# Memory_Display.net
KiCad netlist of a schematic drawn in EAGLE
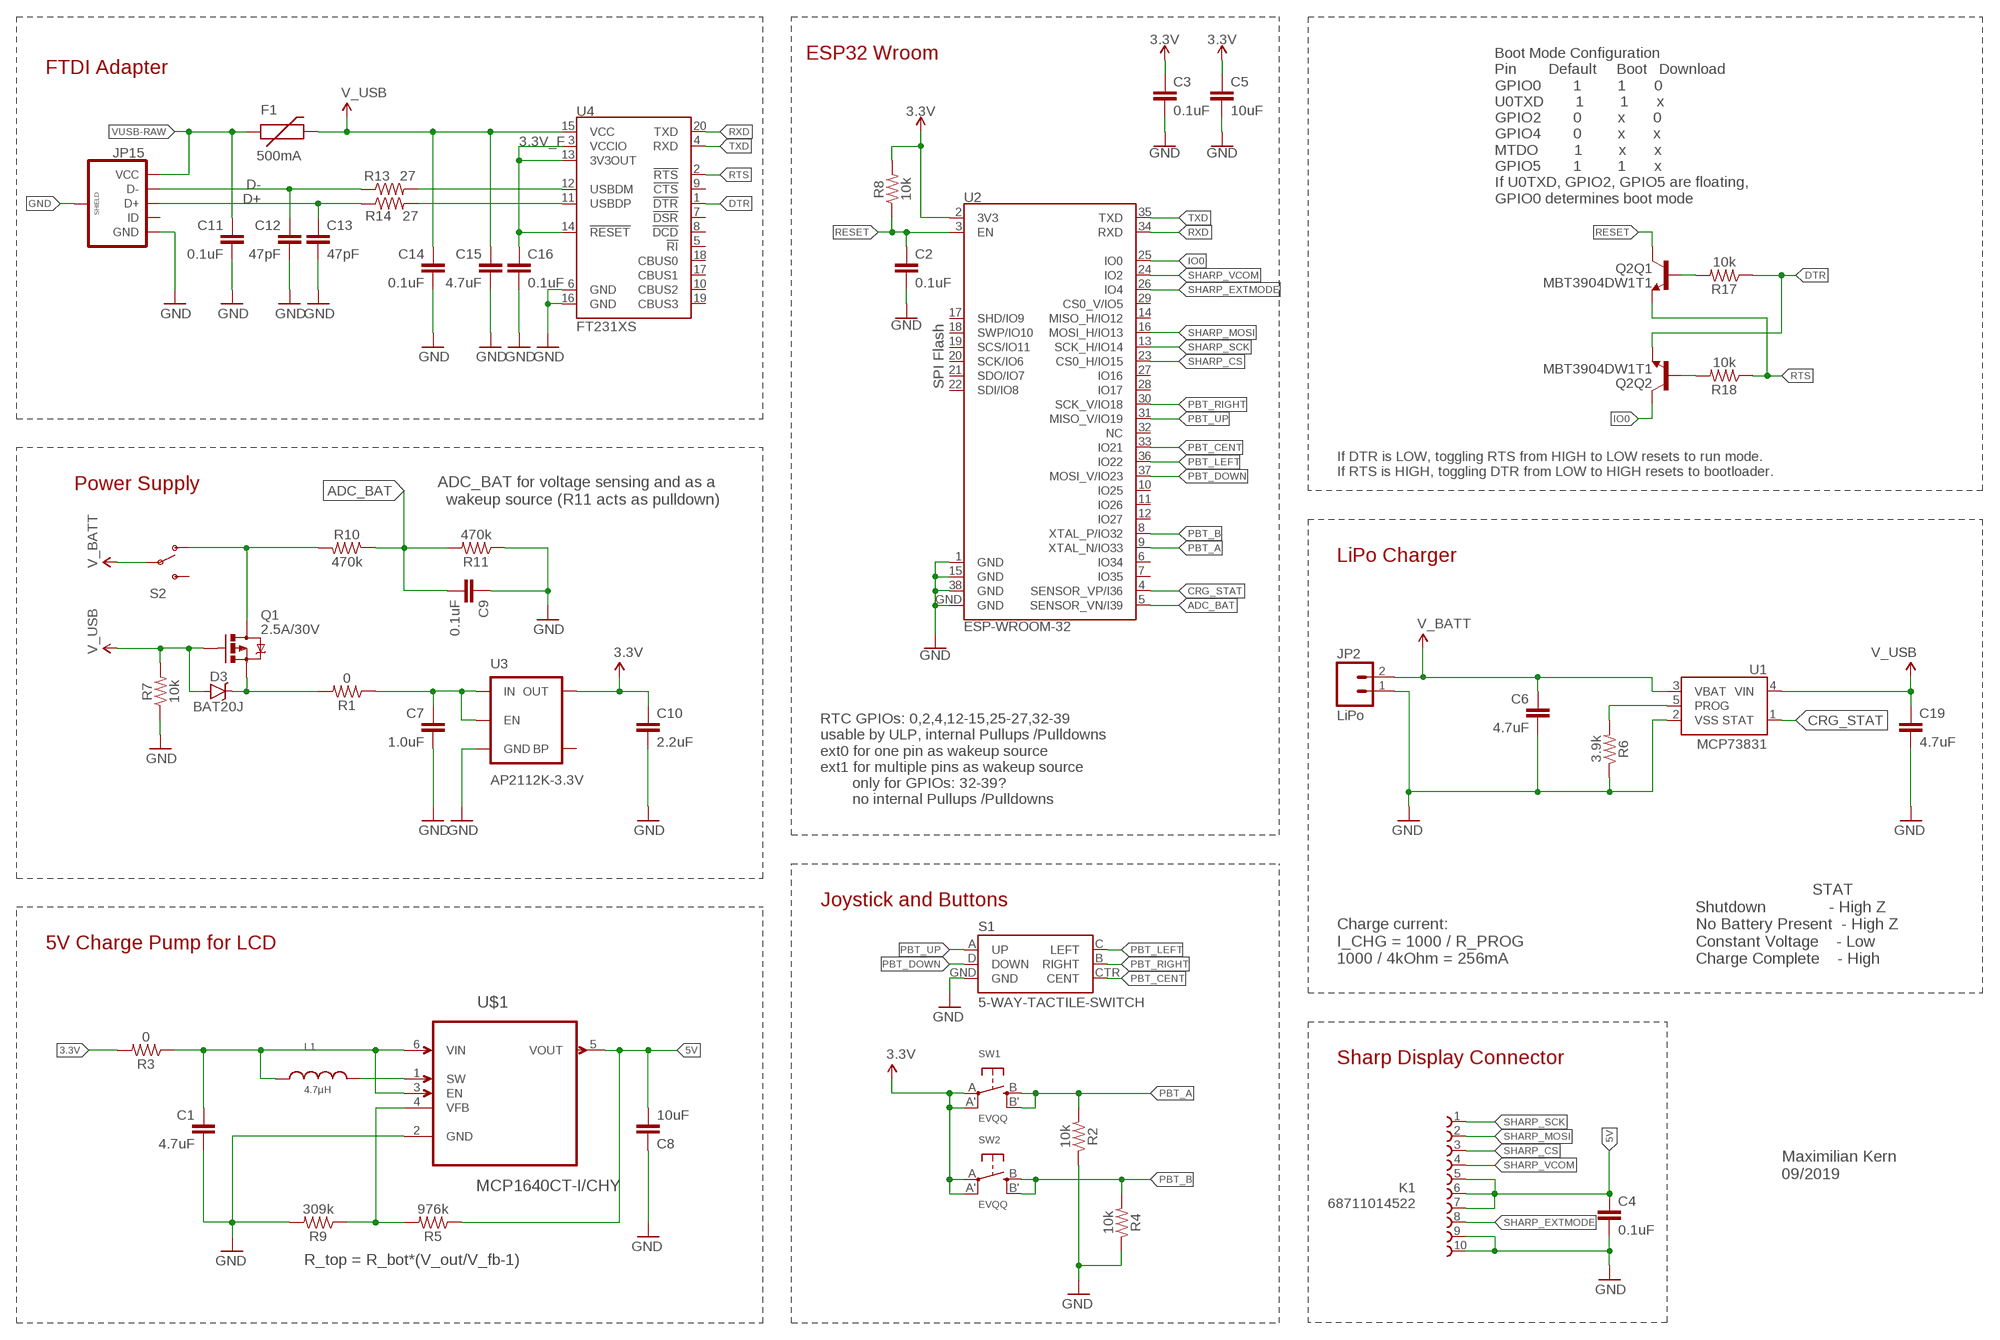
[diagram p0: schematic, sheet 1]

(export (version "E")
  (design (tool "Eeschema 10.0.6"))
  (components
    (comp (ref "C1")
      (value "4.7uF")
      (footprint "eagle-import:0603")
      (libsource (lib "eagle-import") (part "47PF-0603-50V-5%"))
    )
    (comp (ref "C2")
      (value "0.1uF")
      (footprint "eagle-import:0603")
      (libsource (lib "eagle-import") (part "0.1UF-0603-25V-(+80/-20%)"))
    )
    (comp (ref "C3")
      (value "0.1uF")
      (footprint "eagle-import:0603")
      (libsource (lib "eagle-import") (part "0.1UF-0603-25V-(+80/-20%)"))
    )
    (comp (ref "C4")
      (value "0.1uF")
      (footprint "eagle-import:0603")
      (libsource (lib "eagle-import") (part "0.1UF-0603-25V-(+80/-20%)"))
    )
    (comp (ref "C5")
      (value "10uF")
      (footprint "eagle-import:0603")
      (libsource (lib "eagle-import") (part "10UF-0603-6.3V-20%"))
    )
    (comp (ref "C6")
      (value "4.7uF")
      (footprint "eagle-import:0603")
      (libsource (lib "eagle-import") (part "4.7UF0603"))
    )
    (comp (ref "C7")
      (value "1.0uF")
      (footprint "eagle-import:0805")
      (libsource (lib "eagle-import") (part "1.0UF-0805-25V-(+80/-20%)"))
    )
    (comp (ref "C8")
      (value "10uF")
      (footprint "eagle-import:0603")
      (libsource (lib "eagle-import") (part "47PF-0603-50V-5%"))
    )
    (comp (ref "C9")
      (value "0.1uF")
      (footprint "eagle-import:0603")
      (libsource (lib "eagle-import") (part "0.1UF-0603-25V-(+80/-20%)"))
    )
    (comp (ref "C10")
      (value "2.2uF")
      (footprint "eagle-import:0805")
      (libsource (lib "eagle-import") (part "1.0UF-0805-25V-(+80/-20%)"))
    )
    (comp (ref "C11")
      (value "0.1uF")
      (footprint "eagle-import:0603")
      (libsource (lib "eagle-import") (part "0.1UF-0603-25V-(+80/-20%)"))
    )
    (comp (ref "C12")
      (value "47pF")
      (footprint "eagle-import:0603")
      (libsource (lib "eagle-import") (part "47PF-0603-50V-5%"))
    )
    (comp (ref "C13")
      (value "47pF")
      (footprint "eagle-import:0603")
      (libsource (lib "eagle-import") (part "47PF-0603-50V-5%"))
    )
    (comp (ref "C14")
      (value "0.1uF")
      (footprint "eagle-import:0603")
      (libsource (lib "eagle-import") (part "0.1UF-0603-25V-(+80/-20%)"))
    )
    (comp (ref "C15")
      (value "4.7uF")
      (footprint "eagle-import:0603-CAP")
      (libsource (lib "eagle-import") (part "4.7UF-6.3V-10%(0603)0603"))
    )
    (comp (ref "C16")
      (value "0.1uF")
      (footprint "eagle-import:0603")
      (libsource (lib "eagle-import") (part "0.1UF-0603-25V-(+80/-20%)"))
    )
    (comp (ref "C19")
      (value "4.7uF")
      (footprint "eagle-import:0603")
      (libsource (lib "eagle-import") (part "4.7UF0603"))
    )
    (comp (ref "D3")
      (value "BAT20J")
      (footprint "eagle-import:SOD-323")
      (libsource (lib "eagle-import") (part "DIODE-SCHOTTKY-BAT20J"))
    )
    (comp (ref "F1")
      (value "500mA")
      (footprint "eagle-import:PTC-1206")
      (libsource (lib "eagle-import") (part "PTCSMD"))
    )
    (comp (ref "JP2")
      (value "LiPo")
      (footprint "eagle-import:JST-2-PTH")
      (libsource (lib "eagle-import") (part "M02JST-PTH-2"))
    )
    (comp (ref "JP15")
      (value "USB_MICROB_PLUGCONN-11752")
      (footprint "eagle-import:USB-B-MICRO-SMD_V03")
      (libsource (lib "eagle-import") (part "USB_MICROB_PLUGCONN-11752"))
    )
    (comp (ref "K1")
      (value "68711014522")
      (footprint "eagle-import:68711014522")
      (libsource (lib "eagle-import") (part "68711014522"))
    )
    (comp (ref "L1")
      (value "4.7µH")
      (footprint "eagle-import:WE-TPC_2811_2813_OLD")
      (libsource (lib "eagle-import") (part "WE-TPC_2813_744029004"))
    )
    (comp (ref "Q1")
      (value "2.5A/30V")
      (footprint "eagle-import:SOT23-3")
      (libsource (lib "eagle-import") (part "MOSFET-PCHANNELDMG2307L"))
    )
    (comp (ref "Q2")
      (value "MBT3904DW1T1")
      (footprint "eagle-import:SC70-6")
      (libsource (lib "eagle-import") (part "MBT3904DW1T1"))
    )
    (comp (ref "R1")
      (value "0")
      (footprint "eagle-import:0603")
      (libsource (lib "eagle-import") (part "10KOHM-0603-1/10W-1%"))
    )
    (comp (ref "R2")
      (value "10k")
      (footprint "eagle-import:0603")
      (libsource (lib "eagle-import") (part "10KOHM-0603-1/10W-1%"))
    )
    (comp (ref "R3")
      (value "0")
      (footprint "eagle-import:0603")
      (libsource (lib "eagle-import") (part "10KOHM-0603-1/10W-1%"))
    )
    (comp (ref "R4")
      (value "10k")
      (footprint "eagle-import:0603")
      (libsource (lib "eagle-import") (part "10KOHM-0603-1/10W-1%"))
    )
    (comp (ref "R5")
      (value "976k")
      (footprint "eagle-import:0603")
      (libsource (lib "eagle-import") (part "10KOHM-0603-1/10W-1%"))
    )
    (comp (ref "R6")
      (value "3.9k")
      (footprint "eagle-import:0603")
      (libsource (lib "eagle-import") (part "2.0KOHM1/10W5%(0603)"))
    )
    (comp (ref "R7")
      (value "10k")
      (footprint "eagle-import:0603")
      (libsource (lib "eagle-import") (part "10KOHM-0603-1/10W-1%"))
    )
    (comp (ref "R8")
      (value "10k")
      (footprint "eagle-import:0603")
      (libsource (lib "eagle-import") (part "10KOHM-0603-1/10W-1%"))
    )
    (comp (ref "R9")
      (value "309k")
      (footprint "eagle-import:0603")
      (libsource (lib "eagle-import") (part "10KOHM-0603-1/10W-1%"))
    )
    (comp (ref "R10")
      (value "470k")
      (footprint "eagle-import:0603")
      (libsource (lib "eagle-import") (part "10KOHM-0603-1/10W-1%"))
    )
    (comp (ref "R11")
      (value "470k")
      (footprint "eagle-import:0603")
      (libsource (lib "eagle-import") (part "10KOHM-0603-1/10W-1%"))
    )
    (comp (ref "R13")
      (value "27")
      (footprint "eagle-import:0603")
      (libsource (lib "eagle-import") (part "27OHM1/10W1%(0603)0603-RES"))
    )
    (comp (ref "R14")
      (value "27")
      (footprint "eagle-import:0603")
      (libsource (lib "eagle-import") (part "27OHM1/10W1%(0603)0603-RES"))
    )
    (comp (ref "R17")
      (value "10k")
      (footprint "eagle-import:0603")
      (libsource (lib "eagle-import") (part "10KOHM-0603-1/10W-1%"))
    )
    (comp (ref "R18")
      (value "10k")
      (footprint "eagle-import:0603")
      (libsource (lib "eagle-import") (part "10KOHM-0603-1/10W-1%"))
    )
    (comp (ref "S1")
      (value "5-WAY-TACTILE-SWITCH")
      (footprint "eagle-import:JOYSTICK_MINI")
      (libsource (lib "eagle-import") (part "JOYSTICK_MINI"))
    )
    (comp (ref "S2")
      (value "SWITCH-SPDT-SMD-A")
      (footprint "eagle-import:SWITCH-SPST-SMD-A")
      (libsource (lib "eagle-import") (part "SWITCH-SPDT-SMD-A"))
    )
    (comp (ref "SW1")
      (value "EVQQ")
      (footprint "eagle-import:EVQ-Q2_SMALLER")
      (libsource (lib "eagle-import") (part "SWITCH_TACT_SMT_EVQQ2_SMALL"))
    )
    (comp (ref "SW2")
      (value "EVQQ")
      (footprint "eagle-import:EVQ-Q2_SMALLER")
      (libsource (lib "eagle-import") (part "SWITCH_TACT_SMT_EVQQ2_SMALL"))
    )
    (comp (ref "U$1")
      (value "MCP1640CT-I/CHY")
      (footprint "eagle-import:SOT95P270X145-6N")
      (libsource (lib "eagle-import") (part "MCP1640CT-I/CHY"))
    )
    (comp (ref "U1")
      (value "MCP73831")
      (footprint "eagle-import:SOT23-5")
      (libsource (lib "eagle-import") (part "MCP73831"))
    )
    (comp (ref "U2")
      (value "ESP-WROOM-32")
      (footprint "eagle-import:ESP-WROOM-32")
      (libsource (lib "eagle-import") (part "ESP-WROOM-32"))
    )
    (comp (ref "U3")
      (value "AP2112K-3.3V")
      (footprint "eagle-import:SOT23-5")
      (libsource (lib "eagle-import") (part "V_REG_LDOSMD"))
    )
    (comp (ref "U4")
      (value "FT231XS")
      (footprint "eagle-import:SSOP20_L")
      (libsource (lib "eagle-import") (part "FT231XS"))
    )
  )
  (nets
    (net (code "1") (name "/3.3V_F") (class "Default")
      (node (ref "C16") (pin "1") (pinfunction "1_1") (pintype "passive"))
      (node (ref "U4") (pin "13") (pinfunction "3V3OUT_13") (pintype "bidirectional"))
      (node (ref "U4") (pin "14") (pinfunction "~{RESET}_14") (pintype "bidirectional"))
      (node (ref "U4") (pin "3") (pinfunction "VCCIO_3") (pintype "bidirectional"))
    )
    (net (code "2") (name "/D+") (class "Default")
      (node (ref "C13") (pin "1") (pinfunction "1_1") (pintype "passive"))
      (node (ref "JP15") (pin "D+") (pinfunction "D+_D+") (pintype "bidirectional"))
      (node (ref "R14") (pin "1") (pinfunction "1_1") (pintype "passive"))
    )
    (net (code "3") (name "/D-") (class "Default")
      (node (ref "C12") (pin "1") (pinfunction "1_1") (pintype "passive"))
      (node (ref "JP15") (pin "D-") (pinfunction "D-_D-") (pintype "bidirectional"))
      (node (ref "R13") (pin "1") (pinfunction "1_1") (pintype "passive"))
    )
    (net (code "4") (name "3.3V") (class "Default")
      (node (ref "C10") (pin "1") (pinfunction "1_1") (pintype "passive"))
      (node (ref "C3") (pin "1") (pinfunction "1_1") (pintype "passive"))
      (node (ref "C5") (pin "1") (pinfunction "1_1") (pintype "passive"))
      (node (ref "R3") (pin "2") (pinfunction "2_2") (pintype "passive"))
      (node (ref "R8") (pin "2") (pinfunction "2_2") (pintype "passive"))
      (node (ref "SW1") (pin "A") (pinfunction "P_A") (pintype "passive"))
      (node (ref "SW1") (pin "A'") (pinfunction "P1_A'") (pintype "passive"))
      (node (ref "SW2") (pin "A") (pinfunction "P_A") (pintype "passive"))
      (node (ref "SW2") (pin "A'") (pinfunction "P1_A'") (pintype "passive"))
      (node (ref "U2") (pin "2") (pinfunction "3V3_2") (pintype "bidirectional"))
      (node (ref "U3") (pin "5") (pinfunction "OUT_5") (pintype "passive"))
    )
    (net (code "5") (name "5V") (class "Default")
      (node (ref "C4") (pin "1") (pinfunction "1_1") (pintype "passive"))
      (node (ref "C8") (pin "2") (pinfunction "2_2") (pintype "passive"))
      (node (ref "K1") (pin "5") (pinfunction "5_5") (pintype "passive"))
      (node (ref "K1") (pin "6") (pinfunction "6_6") (pintype "passive"))
      (node (ref "K1") (pin "7") (pinfunction "7_7") (pintype "passive"))
      (node (ref "R5") (pin "1") (pinfunction "1_1") (pintype "passive"))
      (node (ref "U$1") (pin "5") (pinfunction "VOUT_5") (pintype "output"))
    )
    (net (code "6") (name "ADC_BAT") (class "Default")
      (node (ref "C9") (pin "2") (pinfunction "2_2") (pintype "passive"))
      (node (ref "R10") (pin "1") (pinfunction "1_1") (pintype "passive"))
      (node (ref "R11") (pin "2") (pinfunction "2_2") (pintype "passive"))
      (node (ref "U2") (pin "5") (pinfunction "SENSOR_VN/I39_5") (pintype "bidirectional"))
    )
    (net (code "7") (name "CRG_STAT") (class "Default")
      (node (ref "U1") (pin "1") (pinfunction "STAT_1") (pintype "output"))
      (node (ref "U2") (pin "4") (pinfunction "SENSOR_VP/I36_4") (pintype "bidirectional"))
    )
    (net (code "8") (name "DTR") (class "Default")
      (node (ref "Q2") (pin "1") (pinfunction "E_1") (pintype "passive"))
      (node (ref "R17") (pin "1") (pinfunction "1_1") (pintype "passive"))
      (node (ref "U4") (pin "1") (pinfunction "~{DTR}_1") (pintype "bidirectional"))
    )
    (net (code "9") (name "GND") (class "Default")
      (node (ref "C1") (pin "2") (pinfunction "2_2") (pintype "passive"))
      (node (ref "C10") (pin "2") (pinfunction "2_2") (pintype "passive"))
      (node (ref "C11") (pin "2") (pinfunction "2_2") (pintype "passive"))
      (node (ref "C12") (pin "2") (pinfunction "2_2") (pintype "passive"))
      (node (ref "C13") (pin "2") (pinfunction "2_2") (pintype "passive"))
      (node (ref "C14") (pin "2") (pinfunction "2_2") (pintype "passive"))
      (node (ref "C15") (pin "2") (pinfunction "2_2") (pintype "passive"))
      (node (ref "C16") (pin "2") (pinfunction "2_2") (pintype "passive"))
      (node (ref "C19") (pin "2") (pinfunction "2_2") (pintype "passive"))
      (node (ref "C2") (pin "2") (pinfunction "2_2") (pintype "passive"))
      (node (ref "C3") (pin "2") (pinfunction "2_2") (pintype "passive"))
      (node (ref "C4") (pin "2") (pinfunction "2_2") (pintype "passive"))
      (node (ref "C5") (pin "2") (pinfunction "2_2") (pintype "passive"))
      (node (ref "C6") (pin "2") (pinfunction "2_2") (pintype "passive"))
      (node (ref "C7") (pin "2") (pinfunction "2_2") (pintype "passive"))
      (node (ref "C8") (pin "1") (pinfunction "1_1") (pintype "passive"))
      (node (ref "C9") (pin "1") (pinfunction "1_1") (pintype "passive"))
      (node (ref "JP15") (pin "GND") (pinfunction "GND_GND") (pintype "bidirectional"))
      (node (ref "JP15") (pin "SHIELD1") (pinfunction "SHIELD_SHIELD1") (pintype "bidirectional"))
      (node (ref "JP15") (pin "SHIELD2") (pinfunction "SHIELD_SHIELD2") (pintype "bidirectional"))
      (node (ref "JP15") (pin "SHIELD3") (pinfunction "SHIELD_SHIELD3") (pintype "bidirectional"))
      (node (ref "JP2") (pin "1") (pinfunction "1_1") (pintype "passive"))
      (node (ref "K1") (pin "10") (pinfunction "10_10") (pintype "passive"))
      (node (ref "K1") (pin "9") (pinfunction "9_9") (pintype "passive"))
      (node (ref "R11") (pin "1") (pinfunction "1_1") (pintype "passive"))
      (node (ref "R2") (pin "1") (pinfunction "1_1") (pintype "passive"))
      (node (ref "R4") (pin "1") (pinfunction "1_1") (pintype "passive"))
      (node (ref "R6") (pin "1") (pinfunction "1_1") (pintype "passive"))
      (node (ref "R7") (pin "1") (pinfunction "1_1") (pintype "passive"))
      (node (ref "R9") (pin "2") (pinfunction "2_2") (pintype "passive"))
      (node (ref "S1") (pin "GND") (pinfunction "GND_GND") (pintype "bidirectional"))
      (node (ref "U$1") (pin "2") (pinfunction "GND_2") (pintype "passive"))
      (node (ref "U1") (pin "2") (pinfunction "VSS_2") (pintype "power_in"))
      (node (ref "U2") (pin "1") (pinfunction "GND_1") (pintype "bidirectional"))
      (node (ref "U2") (pin "15") (pinfunction "GND_15") (pintype "bidirectional"))
      (node (ref "U2") (pin "38") (pinfunction "GND_38") (pintype "bidirectional"))
      (node (ref "U2") (pin "GND") (pinfunction "GND_GND") (pintype "bidirectional"))
      (node (ref "U3") (pin "2") (pinfunction "GND_2") (pintype "input"))
      (node (ref "U4") (pin "16") (pinfunction "GND_16") (pintype "bidirectional"))
      (node (ref "U4") (pin "6") (pinfunction "GND_6") (pintype "bidirectional"))
    )
    (net (code "10") (name "IO0") (class "Default")
      (node (ref "Q2") (pin "6") (pinfunction "C_6") (pintype "passive"))
      (node (ref "U2") (pin "25") (pinfunction "IO0_25") (pintype "bidirectional"))
    )
    (net (code "11") (name "Net-(Q1-D)") (class "Default")
      (node (ref "Q1") (pin "3") (pinfunction "D_3") (pintype "passive"))
      (node (ref "R10") (pin "2") (pinfunction "2_2") (pintype "passive"))
      (node (ref "S2") (pin "1") (pinfunction "O_1") (pintype "passive"))
    )
    (net (code "12") (name "Net-(Q1-S)") (class "Default")
      (node (ref "D3") (pin "C") (pinfunction "C_C") (pintype "passive"))
      (node (ref "Q1") (pin "2") (pinfunction "S_2") (pintype "passive"))
      (node (ref "R1") (pin "2") (pinfunction "2_2") (pintype "passive"))
    )
    (net (code "13") (name "Net-(Q2A-B)") (class "Default")
      (node (ref "Q2") (pin "5") (pinfunction "B_5") (pintype "passive"))
      (node (ref "R17") (pin "2") (pinfunction "2_2") (pintype "passive"))
    )
    (net (code "14") (name "Net-(Q2B-B)") (class "Default")
      (node (ref "Q2") (pin "2") (pinfunction "B_2") (pintype "passive"))
      (node (ref "R18") (pin "2") (pinfunction "2_2") (pintype "passive"))
    )
    (net (code "15") (name "Net-(U$1-EN)") (class "Default")
      (node (ref "C1") (pin "1") (pinfunction "1_1") (pintype "passive"))
      (node (ref "L1") (pin "1") (pinfunction "1_1") (pintype "passive"))
      (node (ref "R3") (pin "1") (pinfunction "1_1") (pintype "passive"))
      (node (ref "U$1") (pin "3") (pinfunction "EN_3") (pintype "input"))
      (node (ref "U$1") (pin "6") (pinfunction "VIN_6") (pintype "input"))
    )
    (net (code "16") (name "Net-(U$1-SW)") (class "Default")
      (node (ref "L1") (pin "2") (pinfunction "2_2") (pintype "passive"))
      (node (ref "U$1") (pin "1") (pinfunction "SW_1") (pintype "input"))
    )
    (net (code "17") (name "Net-(U$1-VFB)") (class "Default")
      (node (ref "R5") (pin "2") (pinfunction "2_2") (pintype "passive"))
      (node (ref "R9") (pin "1") (pinfunction "1_1") (pintype "passive"))
      (node (ref "U$1") (pin "4") (pinfunction "VFB_4") (pintype "input"))
    )
    (net (code "18") (name "Net-(U1-PROG)") (class "Default")
      (node (ref "R6") (pin "2") (pinfunction "2_2") (pintype "passive"))
      (node (ref "U1") (pin "5") (pinfunction "PROG_5") (pintype "input"))
    )
    (net (code "19") (name "Net-(U3-EN)") (class "Default")
      (node (ref "C7") (pin "1") (pinfunction "1_1") (pintype "passive"))
      (node (ref "R1") (pin "1") (pinfunction "1_1") (pintype "passive"))
      (node (ref "U3") (pin "1") (pinfunction "IN_1") (pintype "input"))
      (node (ref "U3") (pin "3") (pinfunction "EN_3") (pintype "input"))
    )
    (net (code "20") (name "Net-(U4-USBDM)") (class "Default")
      (node (ref "R13") (pin "2") (pinfunction "2_2") (pintype "passive"))
      (node (ref "U4") (pin "12") (pinfunction "USBDM_12") (pintype "bidirectional"))
    )
    (net (code "21") (name "Net-(U4-USBDP)") (class "Default")
      (node (ref "R14") (pin "2") (pinfunction "2_2") (pintype "passive"))
      (node (ref "U4") (pin "11") (pinfunction "USBDP_11") (pintype "bidirectional"))
    )
    (net (code "22") (name "PBT_A") (class "Default")
      (node (ref "R2") (pin "2") (pinfunction "2_2") (pintype "passive"))
      (node (ref "SW1") (pin "B") (pinfunction "S_B") (pintype "passive"))
      (node (ref "SW1") (pin "B'") (pinfunction "S1_B'") (pintype "passive"))
      (node (ref "U2") (pin "9") (pinfunction "XTAL_N/IO33_9") (pintype "bidirectional"))
    )
    (net (code "23") (name "PBT_B") (class "Default")
      (node (ref "R4") (pin "2") (pinfunction "2_2") (pintype "passive"))
      (node (ref "SW2") (pin "B") (pinfunction "S_B") (pintype "passive"))
      (node (ref "SW2") (pin "B'") (pinfunction "S1_B'") (pintype "passive"))
      (node (ref "U2") (pin "8") (pinfunction "XTAL_P/IO32_8") (pintype "bidirectional"))
    )
    (net (code "24") (name "PBT_CENT") (class "Default")
      (node (ref "S1") (pin "CTR") (pinfunction "CENT_CTR") (pintype "bidirectional"))
      (node (ref "U2") (pin "33") (pinfunction "IO21_33") (pintype "bidirectional"))
    )
    (net (code "25") (name "PBT_DOWN") (class "Default")
      (node (ref "S1") (pin "D") (pinfunction "DOWN_D") (pintype "bidirectional"))
      (node (ref "U2") (pin "37") (pinfunction "MOSI_V/IO23_37") (pintype "bidirectional"))
    )
    (net (code "26") (name "PBT_LEFT") (class "Default")
      (node (ref "S1") (pin "C") (pinfunction "LEFT_C") (pintype "bidirectional"))
      (node (ref "U2") (pin "36") (pinfunction "IO22_36") (pintype "bidirectional"))
    )
    (net (code "27") (name "PBT_RIGHT") (class "Default")
      (node (ref "S1") (pin "B") (pinfunction "RIGHT_B") (pintype "bidirectional"))
      (node (ref "U2") (pin "30") (pinfunction "SCK_V/IO18_30") (pintype "bidirectional"))
    )
    (net (code "28") (name "PBT_UP") (class "Default")
      (node (ref "S1") (pin "A") (pinfunction "UP_A") (pintype "bidirectional"))
      (node (ref "U2") (pin "31") (pinfunction "MISO_V/IO19_31") (pintype "bidirectional"))
    )
    (net (code "29") (name "RESET") (class "Default")
      (node (ref "C2") (pin "1") (pinfunction "1_1") (pintype "passive"))
      (node (ref "Q2") (pin "3") (pinfunction "C_3") (pintype "passive"))
      (node (ref "R8") (pin "1") (pinfunction "1_1") (pintype "passive"))
      (node (ref "U2") (pin "3") (pinfunction "EN_3") (pintype "bidirectional"))
    )
    (net (code "30") (name "RTS") (class "Default")
      (node (ref "Q2") (pin "4") (pinfunction "E_4") (pintype "passive"))
      (node (ref "R18") (pin "1") (pinfunction "1_1") (pintype "passive"))
      (node (ref "U4") (pin "2") (pinfunction "~{RTS}_2") (pintype "bidirectional"))
    )
    (net (code "31") (name "RXD") (class "Default")
      (node (ref "U2") (pin "34") (pinfunction "RXD_34") (pintype "bidirectional"))
      (node (ref "U4") (pin "20") (pinfunction "TXD_20") (pintype "bidirectional"))
    )
    (net (code "32") (name "SHARP_CS") (class "Default")
      (node (ref "K1") (pin "3") (pinfunction "3_3") (pintype "passive"))
      (node (ref "U2") (pin "23") (pinfunction "CS0_H/IO15_23") (pintype "bidirectional"))
    )
    (net (code "33") (name "SHARP_EXTMODE") (class "Default")
      (node (ref "K1") (pin "8") (pinfunction "8_8") (pintype "passive"))
      (node (ref "U2") (pin "26") (pinfunction "IO4_26") (pintype "bidirectional"))
    )
    (net (code "34") (name "SHARP_MOSI") (class "Default")
      (node (ref "K1") (pin "2") (pinfunction "2_2") (pintype "passive"))
      (node (ref "U2") (pin "16") (pinfunction "MOSI_H/IO13_16") (pintype "bidirectional"))
    )
    (net (code "35") (name "SHARP_SCK") (class "Default")
      (node (ref "K1") (pin "1") (pinfunction "1_1") (pintype "passive"))
      (node (ref "U2") (pin "13") (pinfunction "SCK_H/IO14_13") (pintype "bidirectional"))
    )
    (net (code "36") (name "SHARP_VCOM") (class "Default")
      (node (ref "K1") (pin "4") (pinfunction "4_4") (pintype "passive"))
      (node (ref "U2") (pin "24") (pinfunction "IO2_24") (pintype "bidirectional"))
    )
    (net (code "37") (name "TXD") (class "Default")
      (node (ref "U2") (pin "35") (pinfunction "TXD_35") (pintype "bidirectional"))
      (node (ref "U4") (pin "4") (pinfunction "RXD_4") (pintype "bidirectional"))
    )
    (net (code "38") (name "VUSB-RAW") (class "Default")
      (node (ref "C11") (pin "1") (pinfunction "1_1") (pintype "passive"))
      (node (ref "F1") (pin "1") (pinfunction "1_1") (pintype "bidirectional"))
      (node (ref "JP15") (pin "VBUS") (pinfunction "VCC_VBUS") (pintype "bidirectional"))
    )
    (net (code "39") (name "V_BATT") (class "Default")
      (node (ref "C6") (pin "1") (pinfunction "1_1") (pintype "passive"))
      (node (ref "JP2") (pin "2") (pinfunction "2_2") (pintype "passive"))
      (node (ref "S2") (pin "2") (pinfunction "P_2") (pintype "passive"))
      (node (ref "U1") (pin "3") (pinfunction "VBAT_3") (pintype "power_in"))
    )
    (net (code "40") (name "V_USB") (class "Default")
      (node (ref "C14") (pin "1") (pinfunction "1_1") (pintype "passive"))
      (node (ref "C15") (pin "1") (pinfunction "1_1") (pintype "passive"))
      (node (ref "C19") (pin "1") (pinfunction "1_1") (pintype "passive"))
      (node (ref "D3") (pin "A") (pinfunction "A_A") (pintype "passive"))
      (node (ref "F1") (pin "2") (pinfunction "2_2") (pintype "bidirectional"))
      (node (ref "Q1") (pin "1") (pinfunction "G_1") (pintype "passive"))
      (node (ref "R7") (pin "2") (pinfunction "2_2") (pintype "passive"))
      (node (ref "U1") (pin "4") (pinfunction "VIN_4") (pintype "power_in"))
      (node (ref "U4") (pin "15") (pinfunction "VCC_15") (pintype "bidirectional"))
    )
    (net (code "41") (name "unconnected-(JP15-PadID)") (class "Default")
      (node (ref "JP15") (pin "ID") (pinfunction "ID_ID") (pintype "bidirectional"))
    )
    (net (code "42") (name "unconnected-(S2-S-Pad3)") (class "Default")
      (node (ref "S2") (pin "3") (pinfunction "S_3") (pintype "passive"))
    )
    (net (code "43") (name "unconnected-(U2-CS0_V{slash}IO5-Pad29)") (class "Default")
      (node (ref "U2") (pin "29") (pinfunction "CS0_V/IO5_29") (pintype "bidirectional"))
    )
    (net (code "44") (name "unconnected-(U2-IO16-Pad27)") (class "Default")
      (node (ref "U2") (pin "27") (pinfunction "IO16_27") (pintype "bidirectional"))
    )
    (net (code "45") (name "unconnected-(U2-IO17-Pad28)") (class "Default")
      (node (ref "U2") (pin "28") (pinfunction "IO17_28") (pintype "bidirectional"))
    )
    (net (code "46") (name "unconnected-(U2-IO25-Pad10)") (class "Default")
      (node (ref "U2") (pin "10") (pinfunction "IO25_10") (pintype "bidirectional"))
    )
    (net (code "47") (name "unconnected-(U2-IO26-Pad11)") (class "Default")
      (node (ref "U2") (pin "11") (pinfunction "IO26_11") (pintype "bidirectional"))
    )
    (net (code "48") (name "unconnected-(U2-IO27-Pad12)") (class "Default")
      (node (ref "U2") (pin "12") (pinfunction "IO27_12") (pintype "bidirectional"))
    )
    (net (code "49") (name "unconnected-(U2-IO34-Pad6)") (class "Default")
      (node (ref "U2") (pin "6") (pinfunction "IO34_6") (pintype "bidirectional"))
    )
    (net (code "50") (name "unconnected-(U2-IO35-Pad7)") (class "Default")
      (node (ref "U2") (pin "7") (pinfunction "IO35_7") (pintype "bidirectional"))
    )
    (net (code "51") (name "unconnected-(U2-MISO_H{slash}IO12-Pad14)") (class "Default")
      (node (ref "U2") (pin "14") (pinfunction "MISO_H/IO12_14") (pintype "bidirectional"))
    )
    (net (code "52") (name "unconnected-(U2-NC-Pad32)") (class "Default")
      (node (ref "U2") (pin "32") (pinfunction "NC_32") (pintype "bidirectional"))
    )
    (net (code "53") (name "unconnected-(U2-SCK{slash}IO6-Pad20)") (class "Default")
      (node (ref "U2") (pin "20") (pinfunction "SCK/IO6_20") (pintype "bidirectional"))
    )
    (net (code "54") (name "unconnected-(U2-SCS{slash}IO11-Pad19)") (class "Default")
      (node (ref "U2") (pin "19") (pinfunction "SCS/IO11_19") (pintype "bidirectional"))
    )
    (net (code "55") (name "unconnected-(U2-SDI{slash}IO8-Pad22)") (class "Default")
      (node (ref "U2") (pin "22") (pinfunction "SDI/IO8_22") (pintype "bidirectional"))
    )
    (net (code "56") (name "unconnected-(U2-SDO{slash}IO7-Pad21)") (class "Default")
      (node (ref "U2") (pin "21") (pinfunction "SDO/IO7_21") (pintype "bidirectional"))
    )
    (net (code "57") (name "unconnected-(U2-SHD{slash}IO9-Pad17)") (class "Default")
      (node (ref "U2") (pin "17") (pinfunction "SHD/IO9_17") (pintype "bidirectional"))
    )
    (net (code "58") (name "unconnected-(U2-SWP{slash}IO10-Pad18)") (class "Default")
      (node (ref "U2") (pin "18") (pinfunction "SWP/IO10_18") (pintype "bidirectional"))
    )
    (net (code "59") (name "unconnected-(U3-BP-Pad4)") (class "Default")
      (node (ref "U3") (pin "4") (pinfunction "BP_4") (pintype "input"))
    )
    (net (code "60") (name "unconnected-(U4-CBUS0-Pad18)") (class "Default")
      (node (ref "U4") (pin "18") (pinfunction "CBUS0_18") (pintype "bidirectional"))
    )
    (net (code "61") (name "unconnected-(U4-CBUS1-Pad17)") (class "Default")
      (node (ref "U4") (pin "17") (pinfunction "CBUS1_17") (pintype "bidirectional"))
    )
    (net (code "62") (name "unconnected-(U4-CBUS2-Pad10)") (class "Default")
      (node (ref "U4") (pin "10") (pinfunction "CBUS2_10") (pintype "bidirectional"))
    )
    (net (code "63") (name "unconnected-(U4-CBUS3-Pad19)") (class "Default")
      (node (ref "U4") (pin "19") (pinfunction "CBUS3_19") (pintype "bidirectional"))
    )
    (net (code "64") (name "unconnected-(U4-~{CTS}-Pad9)") (class "Default")
      (node (ref "U4") (pin "9") (pinfunction "~{CTS}_9") (pintype "bidirectional"))
    )
    (net (code "65") (name "unconnected-(U4-~{DCD}-Pad8)") (class "Default")
      (node (ref "U4") (pin "8") (pinfunction "~{DCD}_8") (pintype "bidirectional"))
    )
    (net (code "66") (name "unconnected-(U4-~{DSR}-Pad7)") (class "Default")
      (node (ref "U4") (pin "7") (pinfunction "~{DSR}_7") (pintype "bidirectional"))
    )
    (net (code "67") (name "unconnected-(U4-~{RI}-Pad5)") (class "Default")
      (node (ref "U4") (pin "5") (pinfunction "~{RI}_5") (pintype "bidirectional"))
    )
  )
)
